# Tipper_Remote_Base_Unit.net
KiCad netlist of a schematic drawn in EAGLE
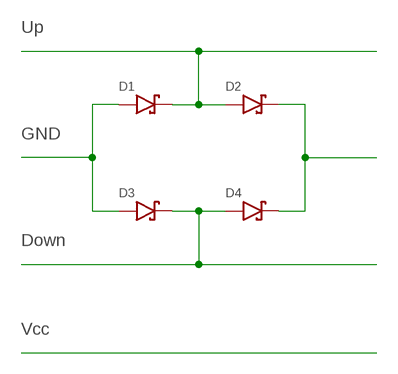
[diagram p0: schematic, sheet 1]

(export (version "E")
  (design (tool "Eeschema 10.0.6"))
  (components
    (comp (ref "D1")
      (value "DIODE-SCHOTTKY-20SQ045")
      (footprint "eagle-import:DIODE_R-6")
      (libsource (lib "eagle-import") (part "DIODE-SCHOTTKY-20SQ045"))
    )
    (comp (ref "D2")
      (value "DIODE-SCHOTTKY-20SQ045")
      (footprint "eagle-import:DIODE_R-6")
      (libsource (lib "eagle-import") (part "DIODE-SCHOTTKY-20SQ045"))
    )
    (comp (ref "D3")
      (value "DIODE-SCHOTTKY-20SQ045")
      (footprint "eagle-import:DIODE_R-6")
      (libsource (lib "eagle-import") (part "DIODE-SCHOTTKY-20SQ045"))
    )
    (comp (ref "D4")
      (value "DIODE-SCHOTTKY-20SQ045")
      (footprint "eagle-import:DIODE_R-6")
      (libsource (lib "eagle-import") (part "DIODE-SCHOTTKY-20SQ045"))
    )
  )
  (nets
    (net (code "1") (name "Net-(D1-PadA)") (class "Default")
      (node (ref "D1") (pin "A") (pinfunction "A_A") (pintype "passive"))
      (node (ref "D3") (pin "A") (pinfunction "A_A") (pintype "passive"))
    )
    (net (code "2") (name "Net-(D1-PadC)") (class "Default")
      (node (ref "D1") (pin "C") (pinfunction "C_C") (pintype "passive"))
      (node (ref "D2") (pin "A") (pinfunction "A_A") (pintype "passive"))
    )
    (net (code "3") (name "Net-(D2-PadC)") (class "Default")
      (node (ref "D2") (pin "C") (pinfunction "C_C") (pintype "passive"))
      (node (ref "D4") (pin "C") (pinfunction "C_C") (pintype "passive"))
    )
    (net (code "4") (name "Net-(D3-PadC)") (class "Default")
      (node (ref "D3") (pin "C") (pinfunction "C_C") (pintype "passive"))
      (node (ref "D4") (pin "A") (pinfunction "A_A") (pintype "passive"))
    )
  )
)
